# 3723_connectors.net
KiCad netlist of a schematic drawn in Altium Designer
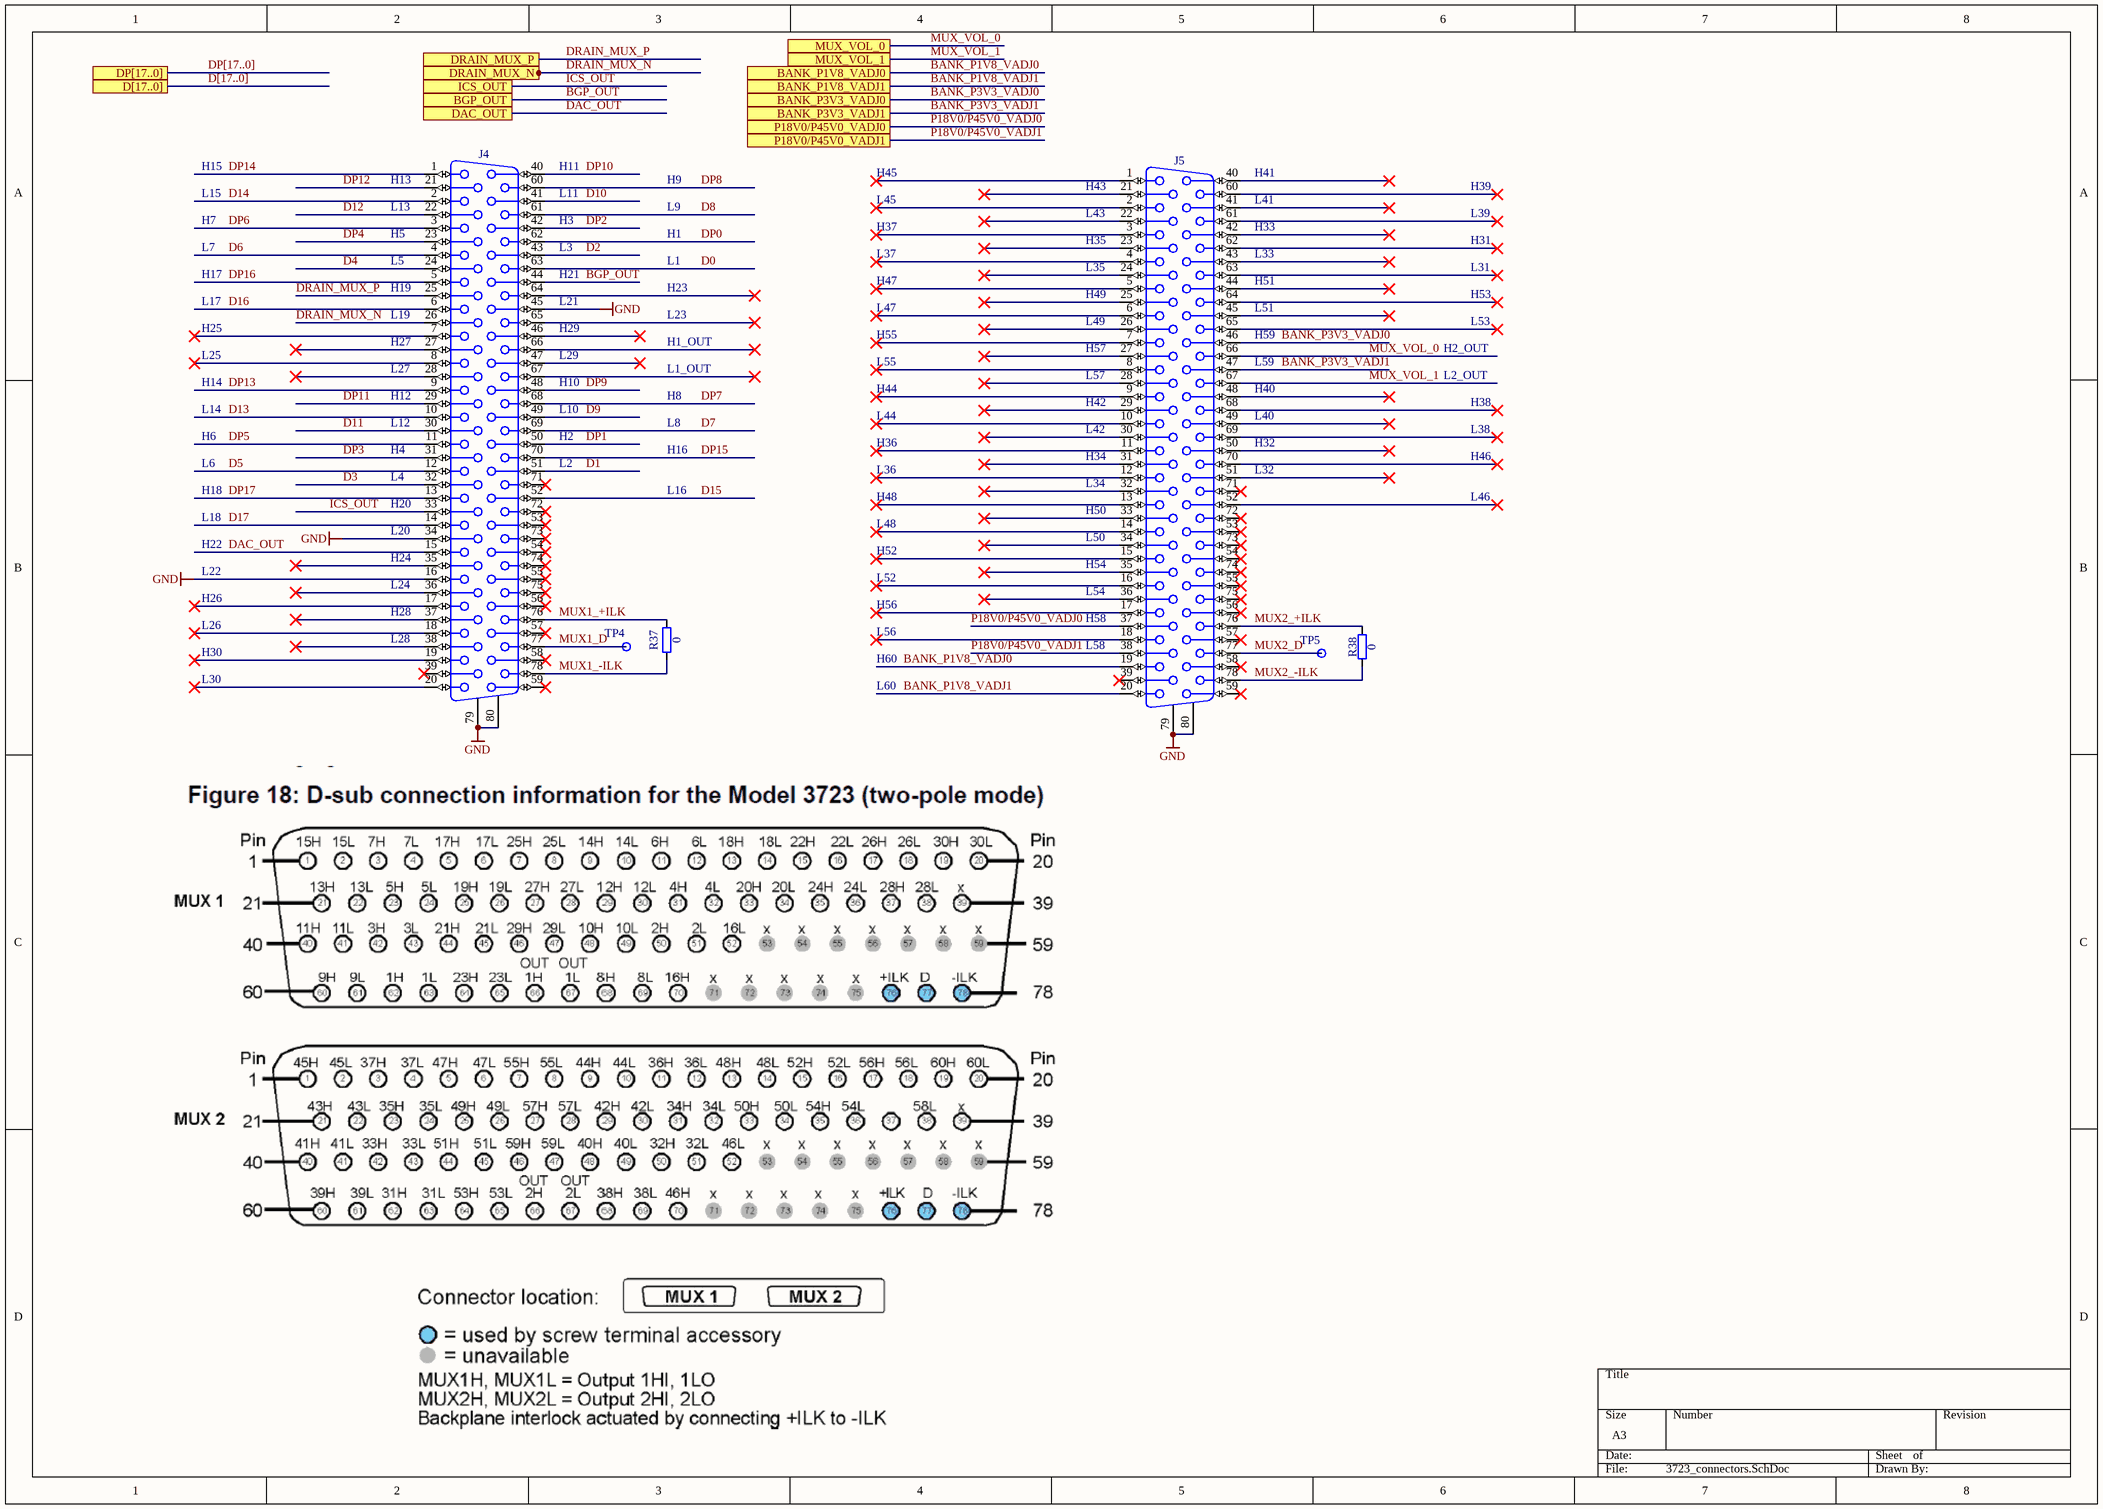
[diagram p0: 3723_connectors.SchDoc]

(export (version "E")
  (design (tool "Eeschema 10.0.6"))
  (components
    (comp (ref "J4")
      (value "D-Sub 78F")
      (footprint "HARTING_09 56 551 7513")
      (description "Connector D-sub 78 Female")
      (fields
        (field (name "PART NUMBER") "HARTING_09 56 551 7513")
        (field (name "MANUFACTURER") "HARTING")
        (field (name "AUTHOR") "CERN DEM JLC")
      )
      (libsource (lib "Connectors") (part "Connector D-sub 78 Female"))
    )
    (comp (ref "J5")
      (value "D-Sub 78F")
      (footprint "HARTING_09 56 551 7513")
      (description "Connector D-sub 78 Female")
      (fields
        (field (name "PART NUMBER") "HARTING_09 56 551 7513")
        (field (name "MANUFACTURER") "HARTING")
        (field (name "AUTHOR") "CERN DEM JLC")
      )
      (libsource (lib "Connectors") (part "Connector D-sub 78 Female"))
    )
    (comp (ref "R37")
      (value "0")
      (footprint "RESC1005X40N")
      (description "Resistor")
      (fields
        (field (name "PART NUMBER") "R0402_0R_JUMPER")
        (field (name "MANUFACTURER") "GENERIC")
        (field (name "AUTHOR") "CERN DEM JLC")
      )
      (libsource (lib "Resistors") (part "Resistor"))
    )
    (comp (ref "R38")
      (value "0")
      (footprint "RESC1005X40N")
      (description "Resistor")
      (fields
        (field (name "PART NUMBER") "R0402_0R_JUMPER")
        (field (name "MANUFACTURER") "GENERIC")
        (field (name "AUTHOR") "CERN DEM JLC")
      )
      (libsource (lib "Resistors") (part "Resistor"))
    )
    (comp (ref "TP4")
      (value "Test Point")
      (footprint "TPS127")
      (fields (field (name "PART NUMBER") "SMD_PAD_1.27X1.27MM") (field (name "AUTHOR") "CERN DEM JLC"))
      (libsource (lib "Eletro-mechanical") (part "Test Point"))
    )
    (comp (ref "TP5")
      (value "Test Point")
      (footprint "TPS127")
      (fields (field (name "PART NUMBER") "SMD_PAD_1.27X1.27MM") (field (name "AUTHOR") "CERN DEM JLC"))
      (libsource (lib "Eletro-mechanical") (part "Test Point"))
    )
  )
  (nets
    (net (code "1") (name "/BANK_P1V8_VADJ0") (class "Default")
      (node (ref "J5") (pin "19") (pinfunction "19_19") (pintype "bidirectional"))
    )
    (net (code "2") (name "/BANK_P1V8_VADJ1") (class "Default")
      (node (ref "J5") (pin "20") (pinfunction "20_20") (pintype "bidirectional"))
    )
    (net (code "3") (name "/BANK_P3V3_VADJ0") (class "Default")
      (node (ref "J5") (pin "46") (pinfunction "46_46") (pintype "bidirectional"))
    )
    (net (code "4") (name "/BANK_P3V3_VADJ1") (class "Default")
      (node (ref "J5") (pin "47") (pinfunction "47_47") (pintype "bidirectional"))
    )
    (net (code "5") (name "/BGP_OUT") (class "Default")
      (node (ref "J4") (pin "44") (pinfunction "44_44") (pintype "bidirectional"))
    )
    (net (code "6") (name "/D0") (class "Default")
      (node (ref "J4") (pin "63") (pinfunction "63_63") (pintype "bidirectional"))
    )
    (net (code "7") (name "/D1") (class "Default")
      (node (ref "J4") (pin "51") (pinfunction "51_51") (pintype "bidirectional"))
    )
    (net (code "8") (name "/D2") (class "Default")
      (node (ref "J4") (pin "43") (pinfunction "43_43") (pintype "bidirectional"))
    )
    (net (code "9") (name "/D3") (class "Default")
      (node (ref "J4") (pin "32") (pinfunction "32_32") (pintype "bidirectional"))
    )
    (net (code "10") (name "/D4") (class "Default")
      (node (ref "J4") (pin "24") (pinfunction "24_24") (pintype "bidirectional"))
    )
    (net (code "11") (name "/D5") (class "Default")
      (node (ref "J4") (pin "12") (pinfunction "12_12") (pintype "bidirectional"))
    )
    (net (code "12") (name "/D6") (class "Default")
      (node (ref "J4") (pin "4") (pinfunction "4_4") (pintype "bidirectional"))
    )
    (net (code "13") (name "/D7") (class "Default")
      (node (ref "J4") (pin "69") (pinfunction "69_69") (pintype "bidirectional"))
    )
    (net (code "14") (name "/D8") (class "Default")
      (node (ref "J4") (pin "61") (pinfunction "61_61") (pintype "bidirectional"))
    )
    (net (code "15") (name "/D9") (class "Default")
      (node (ref "J4") (pin "49") (pinfunction "49_49") (pintype "bidirectional"))
    )
    (net (code "16") (name "/D10") (class "Default")
      (node (ref "J4") (pin "41") (pinfunction "41_41") (pintype "bidirectional"))
    )
    (net (code "17") (name "/D11") (class "Default")
      (node (ref "J4") (pin "30") (pinfunction "30_30") (pintype "bidirectional"))
    )
    (net (code "18") (name "/D12") (class "Default")
      (node (ref "J4") (pin "22") (pinfunction "22_22") (pintype "bidirectional"))
    )
    (net (code "19") (name "/D13") (class "Default")
      (node (ref "J4") (pin "10") (pinfunction "10_10") (pintype "bidirectional"))
    )
    (net (code "20") (name "/D14") (class "Default")
      (node (ref "J4") (pin "2") (pinfunction "2_2") (pintype "bidirectional"))
    )
    (net (code "21") (name "/D15") (class "Default")
      (node (ref "J4") (pin "52") (pinfunction "52_52") (pintype "bidirectional"))
    )
    (net (code "22") (name "/D16") (class "Default")
      (node (ref "J4") (pin "6") (pinfunction "6_6") (pintype "bidirectional"))
    )
    (net (code "23") (name "/D17") (class "Default")
      (node (ref "J4") (pin "14") (pinfunction "14_14") (pintype "bidirectional"))
    )
    (net (code "24") (name "/DAC_OUT") (class "Default")
      (node (ref "J4") (pin "15") (pinfunction "15_15") (pintype "bidirectional"))
    )
    (net (code "25") (name "/DP0") (class "Default")
      (node (ref "J4") (pin "62") (pinfunction "62_62") (pintype "bidirectional"))
    )
    (net (code "26") (name "/DP1") (class "Default")
      (node (ref "J4") (pin "50") (pinfunction "50_50") (pintype "bidirectional"))
    )
    (net (code "27") (name "/DP2") (class "Default")
      (node (ref "J4") (pin "42") (pinfunction "42_42") (pintype "bidirectional"))
    )
    (net (code "28") (name "/DP3") (class "Default")
      (node (ref "J4") (pin "31") (pinfunction "31_31") (pintype "bidirectional"))
    )
    (net (code "29") (name "/DP4") (class "Default")
      (node (ref "J4") (pin "23") (pinfunction "23_23") (pintype "bidirectional"))
    )
    (net (code "30") (name "/DP5") (class "Default")
      (node (ref "J4") (pin "11") (pinfunction "11_11") (pintype "bidirectional"))
    )
    (net (code "31") (name "/DP6") (class "Default")
      (node (ref "J4") (pin "3") (pinfunction "3_3") (pintype "bidirectional"))
    )
    (net (code "32") (name "/DP7") (class "Default")
      (node (ref "J4") (pin "68") (pinfunction "68_68") (pintype "bidirectional"))
    )
    (net (code "33") (name "/DP8") (class "Default")
      (node (ref "J4") (pin "60") (pinfunction "60_60") (pintype "bidirectional"))
    )
    (net (code "34") (name "/DP9") (class "Default")
      (node (ref "J4") (pin "48") (pinfunction "48_48") (pintype "bidirectional"))
    )
    (net (code "35") (name "/DP10") (class "Default")
      (node (ref "J4") (pin "40") (pinfunction "40_40") (pintype "bidirectional"))
    )
    (net (code "36") (name "/DP11") (class "Default")
      (node (ref "J4") (pin "29") (pinfunction "29_29") (pintype "bidirectional"))
    )
    (net (code "37") (name "/DP12") (class "Default")
      (node (ref "J4") (pin "21") (pinfunction "21_21") (pintype "bidirectional"))
    )
    (net (code "38") (name "/DP13") (class "Default")
      (node (ref "J4") (pin "9") (pinfunction "9_9") (pintype "bidirectional"))
    )
    (net (code "39") (name "/DP14") (class "Default")
      (node (ref "J4") (pin "1") (pinfunction "1_1") (pintype "bidirectional"))
    )
    (net (code "40") (name "/DP15") (class "Default")
      (node (ref "J4") (pin "70") (pinfunction "70_70") (pintype "bidirectional"))
    )
    (net (code "41") (name "/DP16") (class "Default")
      (node (ref "J4") (pin "5") (pinfunction "5_5") (pintype "bidirectional"))
    )
    (net (code "42") (name "/DP17") (class "Default")
      (node (ref "J4") (pin "13") (pinfunction "13_13") (pintype "bidirectional"))
    )
    (net (code "44") (name "/DRAIN_MUX_N") (class "Default")
      (node (ref "J4") (pin "26") (pinfunction "26_26") (pintype "bidirectional"))
    )
    (net (code "45") (name "/DRAIN_MUX_P") (class "Default")
      (node (ref "J4") (pin "25") (pinfunction "25_25") (pintype "bidirectional"))
    )
    (net (code "47") (name "/ICS_OUT") (class "Default")
      (node (ref "J4") (pin "33") (pinfunction "33_33") (pintype "bidirectional"))
    )
    (net (code "48") (name "/MUX1_+ILK") (class "Default")
      (node (ref "J4") (pin "76") (pinfunction "76_76") (pintype "bidirectional"))
      (node (ref "R37") (pin "2") (pinfunction "2_2") (pintype "passive"))
    )
    (net (code "49") (name "/MUX1_-ILK") (class "Default")
      (node (ref "J4") (pin "78") (pinfunction "78_78") (pintype "bidirectional"))
      (node (ref "R37") (pin "1") (pinfunction "1_1") (pintype "passive"))
    )
    (net (code "50") (name "/MUX1_D") (class "Default")
      (node (ref "J4") (pin "77") (pinfunction "77_77") (pintype "bidirectional"))
      (node (ref "TP4") (pin "1") (pinfunction "1_1") (pintype "bidirectional"))
    )
    (net (code "51") (name "/MUX2_+ILK") (class "Default")
      (node (ref "J5") (pin "76") (pinfunction "76_76") (pintype "bidirectional"))
      (node (ref "R38") (pin "2") (pinfunction "2_2") (pintype "passive"))
    )
    (net (code "52") (name "/MUX2_-ILK") (class "Default")
      (node (ref "J5") (pin "78") (pinfunction "78_78") (pintype "bidirectional"))
      (node (ref "R38") (pin "1") (pinfunction "1_1") (pintype "passive"))
    )
    (net (code "53") (name "/MUX2_D") (class "Default")
      (node (ref "J5") (pin "77") (pinfunction "77_77") (pintype "bidirectional"))
      (node (ref "TP5") (pin "1") (pinfunction "1_1") (pintype "bidirectional"))
    )
    (net (code "54") (name "/MUX_VOL_0") (class "Default")
      (node (ref "J5") (pin "66") (pinfunction "66_66") (pintype "bidirectional"))
    )
    (net (code "55") (name "/MUX_VOL_1") (class "Default")
      (node (ref "J5") (pin "67") (pinfunction "67_67") (pintype "bidirectional"))
    )
    (net (code "56") (name "/P18V0{slash}P45V0_VADJ0") (class "Default")
      (node (ref "J5") (pin "37") (pinfunction "37_37") (pintype "bidirectional"))
    )
    (net (code "57") (name "/P18V0{slash}P45V0_VADJ1") (class "Default")
      (node (ref "J5") (pin "38") (pinfunction "38_38") (pintype "bidirectional"))
    )
    (net (code "58") (name "GND") (class "Default")
      (node (ref "J4") (pin "16") (pinfunction "16_16") (pintype "bidirectional"))
      (node (ref "J4") (pin "34") (pinfunction "34_34") (pintype "bidirectional"))
      (node (ref "J4") (pin "45") (pinfunction "45_45") (pintype "bidirectional"))
      (node (ref "J4") (pin "79") (pinfunction "79_79") (pintype "passive"))
      (node (ref "J4") (pin "80") (pinfunction "80_80") (pintype "passive"))
      (node (ref "J5") (pin "79") (pinfunction "79_79") (pintype "passive"))
      (node (ref "J5") (pin "80") (pinfunction "80_80") (pintype "passive"))
    )
    (net (code "59") (name "unconnected-(J4-Pad7)") (class "Default")
      (node (ref "J4") (pin "7") (pinfunction "7_7") (pintype "bidirectional+no_connect"))
    )
    (net (code "60") (name "unconnected-(J4-Pad8)") (class "Default")
      (node (ref "J4") (pin "8") (pinfunction "8_8") (pintype "bidirectional+no_connect"))
    )
    (net (code "61") (name "unconnected-(J4-Pad17)") (class "Default")
      (node (ref "J4") (pin "17") (pinfunction "17_17") (pintype "bidirectional+no_connect"))
    )
    (net (code "62") (name "unconnected-(J4-Pad18)") (class "Default")
      (node (ref "J4") (pin "18") (pinfunction "18_18") (pintype "bidirectional+no_connect"))
    )
    (net (code "63") (name "unconnected-(J4-Pad19)") (class "Default")
      (node (ref "J4") (pin "19") (pinfunction "19_19") (pintype "bidirectional+no_connect"))
    )
    (net (code "64") (name "unconnected-(J4-Pad20)") (class "Default")
      (node (ref "J4") (pin "20") (pinfunction "20_20") (pintype "bidirectional+no_connect"))
    )
    (net (code "65") (name "unconnected-(J4-Pad27)") (class "Default")
      (node (ref "J4") (pin "27") (pinfunction "27_27") (pintype "bidirectional+no_connect"))
    )
    (net (code "66") (name "unconnected-(J4-Pad28)") (class "Default")
      (node (ref "J4") (pin "28") (pinfunction "28_28") (pintype "bidirectional+no_connect"))
    )
    (net (code "67") (name "unconnected-(J4-Pad35)") (class "Default")
      (node (ref "J4") (pin "35") (pinfunction "35_35") (pintype "bidirectional+no_connect"))
    )
    (net (code "68") (name "unconnected-(J4-Pad36)") (class "Default")
      (node (ref "J4") (pin "36") (pinfunction "36_36") (pintype "bidirectional+no_connect"))
    )
    (net (code "69") (name "unconnected-(J4-Pad37)") (class "Default")
      (node (ref "J4") (pin "37") (pinfunction "37_37") (pintype "bidirectional+no_connect"))
    )
    (net (code "70") (name "unconnected-(J4-Pad38)") (class "Default")
      (node (ref "J4") (pin "38") (pinfunction "38_38") (pintype "bidirectional+no_connect"))
    )
    (net (code "71") (name "unconnected-(J4-Pad39)") (class "Default")
      (node (ref "J4") (pin "39") (pinfunction "39_39") (pintype "bidirectional+no_connect"))
    )
    (net (code "72") (name "unconnected-(J4-Pad46)") (class "Default")
      (node (ref "J4") (pin "46") (pinfunction "46_46") (pintype "bidirectional+no_connect"))
    )
    (net (code "73") (name "unconnected-(J4-Pad47)") (class "Default")
      (node (ref "J4") (pin "47") (pinfunction "47_47") (pintype "bidirectional+no_connect"))
    )
    (net (code "74") (name "unconnected-(J4-Pad53)") (class "Default")
      (node (ref "J4") (pin "53") (pinfunction "53_53") (pintype "bidirectional+no_connect"))
    )
    (net (code "75") (name "unconnected-(J4-Pad54)") (class "Default")
      (node (ref "J4") (pin "54") (pinfunction "54_54") (pintype "bidirectional+no_connect"))
    )
    (net (code "76") (name "unconnected-(J4-Pad55)") (class "Default")
      (node (ref "J4") (pin "55") (pinfunction "55_55") (pintype "bidirectional+no_connect"))
    )
    (net (code "77") (name "unconnected-(J4-Pad56)") (class "Default")
      (node (ref "J4") (pin "56") (pinfunction "56_56") (pintype "bidirectional+no_connect"))
    )
    (net (code "78") (name "unconnected-(J4-Pad57)") (class "Default")
      (node (ref "J4") (pin "57") (pinfunction "57_57") (pintype "bidirectional+no_connect"))
    )
    (net (code "79") (name "unconnected-(J4-Pad58)") (class "Default")
      (node (ref "J4") (pin "58") (pinfunction "58_58") (pintype "bidirectional+no_connect"))
    )
    (net (code "80") (name "unconnected-(J4-Pad59)") (class "Default")
      (node (ref "J4") (pin "59") (pinfunction "59_59") (pintype "bidirectional+no_connect"))
    )
    (net (code "81") (name "unconnected-(J4-Pad64)") (class "Default")
      (node (ref "J4") (pin "64") (pinfunction "64_64") (pintype "bidirectional+no_connect"))
    )
    (net (code "82") (name "unconnected-(J4-Pad65)") (class "Default")
      (node (ref "J4") (pin "65") (pinfunction "65_65") (pintype "bidirectional+no_connect"))
    )
    (net (code "83") (name "unconnected-(J4-Pad66)") (class "Default")
      (node (ref "J4") (pin "66") (pinfunction "66_66") (pintype "bidirectional+no_connect"))
    )
    (net (code "84") (name "unconnected-(J4-Pad67)") (class "Default")
      (node (ref "J4") (pin "67") (pinfunction "67_67") (pintype "bidirectional+no_connect"))
    )
    (net (code "85") (name "unconnected-(J4-Pad71)") (class "Default")
      (node (ref "J4") (pin "71") (pinfunction "71_71") (pintype "bidirectional+no_connect"))
    )
    (net (code "86") (name "unconnected-(J4-Pad72)") (class "Default")
      (node (ref "J4") (pin "72") (pinfunction "72_72") (pintype "bidirectional+no_connect"))
    )
    (net (code "87") (name "unconnected-(J4-Pad73)") (class "Default")
      (node (ref "J4") (pin "73") (pinfunction "73_73") (pintype "bidirectional+no_connect"))
    )
    (net (code "88") (name "unconnected-(J4-Pad74)") (class "Default")
      (node (ref "J4") (pin "74") (pinfunction "74_74") (pintype "bidirectional+no_connect"))
    )
    (net (code "89") (name "unconnected-(J4-Pad75)") (class "Default")
      (node (ref "J4") (pin "75") (pinfunction "75_75") (pintype "bidirectional+no_connect"))
    )
    (net (code "90") (name "unconnected-(J5-Pad1)") (class "Default")
      (node (ref "J5") (pin "1") (pinfunction "1_1") (pintype "bidirectional+no_connect"))
    )
    (net (code "91") (name "unconnected-(J5-Pad2)") (class "Default")
      (node (ref "J5") (pin "2") (pinfunction "2_2") (pintype "bidirectional+no_connect"))
    )
    (net (code "92") (name "unconnected-(J5-Pad3)") (class "Default")
      (node (ref "J5") (pin "3") (pinfunction "3_3") (pintype "bidirectional+no_connect"))
    )
    (net (code "93") (name "unconnected-(J5-Pad4)") (class "Default")
      (node (ref "J5") (pin "4") (pinfunction "4_4") (pintype "bidirectional+no_connect"))
    )
    (net (code "94") (name "unconnected-(J5-Pad5)") (class "Default")
      (node (ref "J5") (pin "5") (pinfunction "5_5") (pintype "bidirectional+no_connect"))
    )
    (net (code "95") (name "unconnected-(J5-Pad6)") (class "Default")
      (node (ref "J5") (pin "6") (pinfunction "6_6") (pintype "bidirectional+no_connect"))
    )
    (net (code "96") (name "unconnected-(J5-Pad7)") (class "Default")
      (node (ref "J5") (pin "7") (pinfunction "7_7") (pintype "bidirectional+no_connect"))
    )
    (net (code "97") (name "unconnected-(J5-Pad8)") (class "Default")
      (node (ref "J5") (pin "8") (pinfunction "8_8") (pintype "bidirectional+no_connect"))
    )
    (net (code "98") (name "unconnected-(J5-Pad9)") (class "Default")
      (node (ref "J5") (pin "9") (pinfunction "9_9") (pintype "bidirectional+no_connect"))
    )
    (net (code "99") (name "unconnected-(J5-Pad10)") (class "Default")
      (node (ref "J5") (pin "10") (pinfunction "10_10") (pintype "bidirectional+no_connect"))
    )
    (net (code "100") (name "unconnected-(J5-Pad11)") (class "Default")
      (node (ref "J5") (pin "11") (pinfunction "11_11") (pintype "bidirectional+no_connect"))
    )
    (net (code "101") (name "unconnected-(J5-Pad12)") (class "Default")
      (node (ref "J5") (pin "12") (pinfunction "12_12") (pintype "bidirectional+no_connect"))
    )
    (net (code "102") (name "unconnected-(J5-Pad13)") (class "Default")
      (node (ref "J5") (pin "13") (pinfunction "13_13") (pintype "bidirectional+no_connect"))
    )
    (net (code "103") (name "unconnected-(J5-Pad14)") (class "Default")
      (node (ref "J5") (pin "14") (pinfunction "14_14") (pintype "bidirectional+no_connect"))
    )
    (net (code "104") (name "unconnected-(J5-Pad15)") (class "Default")
      (node (ref "J5") (pin "15") (pinfunction "15_15") (pintype "bidirectional+no_connect"))
    )
    (net (code "105") (name "unconnected-(J5-Pad16)") (class "Default")
      (node (ref "J5") (pin "16") (pinfunction "16_16") (pintype "bidirectional+no_connect"))
    )
    (net (code "106") (name "unconnected-(J5-Pad17)") (class "Default")
      (node (ref "J5") (pin "17") (pinfunction "17_17") (pintype "bidirectional+no_connect"))
    )
    (net (code "107") (name "unconnected-(J5-Pad18)") (class "Default")
      (node (ref "J5") (pin "18") (pinfunction "18_18") (pintype "bidirectional+no_connect"))
    )
    (net (code "108") (name "unconnected-(J5-Pad21)") (class "Default")
      (node (ref "J5") (pin "21") (pinfunction "21_21") (pintype "bidirectional+no_connect"))
    )
    (net (code "109") (name "unconnected-(J5-Pad22)") (class "Default")
      (node (ref "J5") (pin "22") (pinfunction "22_22") (pintype "bidirectional+no_connect"))
    )
    (net (code "110") (name "unconnected-(J5-Pad23)") (class "Default")
      (node (ref "J5") (pin "23") (pinfunction "23_23") (pintype "bidirectional+no_connect"))
    )
    (net (code "111") (name "unconnected-(J5-Pad24)") (class "Default")
      (node (ref "J5") (pin "24") (pinfunction "24_24") (pintype "bidirectional+no_connect"))
    )
    (net (code "112") (name "unconnected-(J5-Pad25)") (class "Default")
      (node (ref "J5") (pin "25") (pinfunction "25_25") (pintype "bidirectional+no_connect"))
    )
    (net (code "113") (name "unconnected-(J5-Pad26)") (class "Default")
      (node (ref "J5") (pin "26") (pinfunction "26_26") (pintype "bidirectional+no_connect"))
    )
    (net (code "114") (name "unconnected-(J5-Pad27)") (class "Default")
      (node (ref "J5") (pin "27") (pinfunction "27_27") (pintype "bidirectional+no_connect"))
    )
    (net (code "115") (name "unconnected-(J5-Pad28)") (class "Default")
      (node (ref "J5") (pin "28") (pinfunction "28_28") (pintype "bidirectional+no_connect"))
    )
    (net (code "116") (name "unconnected-(J5-Pad29)") (class "Default")
      (node (ref "J5") (pin "29") (pinfunction "29_29") (pintype "bidirectional+no_connect"))
    )
    (net (code "117") (name "unconnected-(J5-Pad30)") (class "Default")
      (node (ref "J5") (pin "30") (pinfunction "30_30") (pintype "bidirectional+no_connect"))
    )
    (net (code "118") (name "unconnected-(J5-Pad31)") (class "Default")
      (node (ref "J5") (pin "31") (pinfunction "31_31") (pintype "bidirectional+no_connect"))
    )
    (net (code "119") (name "unconnected-(J5-Pad32)") (class "Default")
      (node (ref "J5") (pin "32") (pinfunction "32_32") (pintype "bidirectional+no_connect"))
    )
    (net (code "120") (name "unconnected-(J5-Pad33)") (class "Default")
      (node (ref "J5") (pin "33") (pinfunction "33_33") (pintype "bidirectional+no_connect"))
    )
    (net (code "121") (name "unconnected-(J5-Pad34)") (class "Default")
      (node (ref "J5") (pin "34") (pinfunction "34_34") (pintype "bidirectional+no_connect"))
    )
    (net (code "122") (name "unconnected-(J5-Pad35)") (class "Default")
      (node (ref "J5") (pin "35") (pinfunction "35_35") (pintype "bidirectional+no_connect"))
    )
    (net (code "123") (name "unconnected-(J5-Pad36)") (class "Default")
      (node (ref "J5") (pin "36") (pinfunction "36_36") (pintype "bidirectional+no_connect"))
    )
    (net (code "124") (name "unconnected-(J5-Pad39)") (class "Default")
      (node (ref "J5") (pin "39") (pinfunction "39_39") (pintype "bidirectional+no_connect"))
    )
    (net (code "125") (name "unconnected-(J5-Pad40)") (class "Default")
      (node (ref "J5") (pin "40") (pinfunction "40_40") (pintype "bidirectional+no_connect"))
    )
    (net (code "126") (name "unconnected-(J5-Pad41)") (class "Default")
      (node (ref "J5") (pin "41") (pinfunction "41_41") (pintype "bidirectional+no_connect"))
    )
    (net (code "127") (name "unconnected-(J5-Pad42)") (class "Default")
      (node (ref "J5") (pin "42") (pinfunction "42_42") (pintype "bidirectional+no_connect"))
    )
    (net (code "128") (name "unconnected-(J5-Pad43)") (class "Default")
      (node (ref "J5") (pin "43") (pinfunction "43_43") (pintype "bidirectional+no_connect"))
    )
    (net (code "129") (name "unconnected-(J5-Pad44)") (class "Default")
      (node (ref "J5") (pin "44") (pinfunction "44_44") (pintype "bidirectional+no_connect"))
    )
    (net (code "130") (name "unconnected-(J5-Pad45)") (class "Default")
      (node (ref "J5") (pin "45") (pinfunction "45_45") (pintype "bidirectional+no_connect"))
    )
    (net (code "131") (name "unconnected-(J5-Pad48)") (class "Default")
      (node (ref "J5") (pin "48") (pinfunction "48_48") (pintype "bidirectional+no_connect"))
    )
    (net (code "132") (name "unconnected-(J5-Pad49)") (class "Default")
      (node (ref "J5") (pin "49") (pinfunction "49_49") (pintype "bidirectional+no_connect"))
    )
    (net (code "133") (name "unconnected-(J5-Pad50)") (class "Default")
      (node (ref "J5") (pin "50") (pinfunction "50_50") (pintype "bidirectional+no_connect"))
    )
    (net (code "134") (name "unconnected-(J5-Pad51)") (class "Default")
      (node (ref "J5") (pin "51") (pinfunction "51_51") (pintype "bidirectional+no_connect"))
    )
    (net (code "135") (name "unconnected-(J5-Pad52)") (class "Default")
      (node (ref "J5") (pin "52") (pinfunction "52_52") (pintype "bidirectional+no_connect"))
    )
    (net (code "136") (name "unconnected-(J5-Pad53)") (class "Default")
      (node (ref "J5") (pin "53") (pinfunction "53_53") (pintype "bidirectional+no_connect"))
    )
    (net (code "137") (name "unconnected-(J5-Pad54)") (class "Default")
      (node (ref "J5") (pin "54") (pinfunction "54_54") (pintype "bidirectional+no_connect"))
    )
    (net (code "138") (name "unconnected-(J5-Pad55)") (class "Default")
      (node (ref "J5") (pin "55") (pinfunction "55_55") (pintype "bidirectional+no_connect"))
    )
    (net (code "139") (name "unconnected-(J5-Pad56)") (class "Default")
      (node (ref "J5") (pin "56") (pinfunction "56_56") (pintype "bidirectional+no_connect"))
    )
    (net (code "140") (name "unconnected-(J5-Pad57)") (class "Default")
      (node (ref "J5") (pin "57") (pinfunction "57_57") (pintype "bidirectional+no_connect"))
    )
    (net (code "141") (name "unconnected-(J5-Pad58)") (class "Default")
      (node (ref "J5") (pin "58") (pinfunction "58_58") (pintype "bidirectional+no_connect"))
    )
    (net (code "142") (name "unconnected-(J5-Pad59)") (class "Default")
      (node (ref "J5") (pin "59") (pinfunction "59_59") (pintype "bidirectional+no_connect"))
    )
    (net (code "143") (name "unconnected-(J5-Pad60)") (class "Default")
      (node (ref "J5") (pin "60") (pinfunction "60_60") (pintype "bidirectional+no_connect"))
    )
    (net (code "144") (name "unconnected-(J5-Pad61)") (class "Default")
      (node (ref "J5") (pin "61") (pinfunction "61_61") (pintype "bidirectional+no_connect"))
    )
    (net (code "145") (name "unconnected-(J5-Pad62)") (class "Default")
      (node (ref "J5") (pin "62") (pinfunction "62_62") (pintype "bidirectional+no_connect"))
    )
    (net (code "146") (name "unconnected-(J5-Pad63)") (class "Default")
      (node (ref "J5") (pin "63") (pinfunction "63_63") (pintype "bidirectional+no_connect"))
    )
    (net (code "147") (name "unconnected-(J5-Pad64)") (class "Default")
      (node (ref "J5") (pin "64") (pinfunction "64_64") (pintype "bidirectional+no_connect"))
    )
    (net (code "148") (name "unconnected-(J5-Pad65)") (class "Default")
      (node (ref "J5") (pin "65") (pinfunction "65_65") (pintype "bidirectional+no_connect"))
    )
    (net (code "149") (name "unconnected-(J5-Pad68)") (class "Default")
      (node (ref "J5") (pin "68") (pinfunction "68_68") (pintype "bidirectional+no_connect"))
    )
    (net (code "150") (name "unconnected-(J5-Pad69)") (class "Default")
      (node (ref "J5") (pin "69") (pinfunction "69_69") (pintype "bidirectional+no_connect"))
    )
    (net (code "151") (name "unconnected-(J5-Pad70)") (class "Default")
      (node (ref "J5") (pin "70") (pinfunction "70_70") (pintype "bidirectional+no_connect"))
    )
    (net (code "152") (name "unconnected-(J5-Pad71)") (class "Default")
      (node (ref "J5") (pin "71") (pinfunction "71_71") (pintype "bidirectional+no_connect"))
    )
    (net (code "153") (name "unconnected-(J5-Pad72)") (class "Default")
      (node (ref "J5") (pin "72") (pinfunction "72_72") (pintype "bidirectional+no_connect"))
    )
    (net (code "154") (name "unconnected-(J5-Pad73)") (class "Default")
      (node (ref "J5") (pin "73") (pinfunction "73_73") (pintype "bidirectional+no_connect"))
    )
    (net (code "155") (name "unconnected-(J5-Pad74)") (class "Default")
      (node (ref "J5") (pin "74") (pinfunction "74_74") (pintype "bidirectional+no_connect"))
    )
    (net (code "156") (name "unconnected-(J5-Pad75)") (class "Default")
      (node (ref "J5") (pin "75") (pinfunction "75_75") (pintype "bidirectional+no_connect"))
    )
  )
)
